# Power.net
KiCad netlist of a schematic drawn in Altium Designer
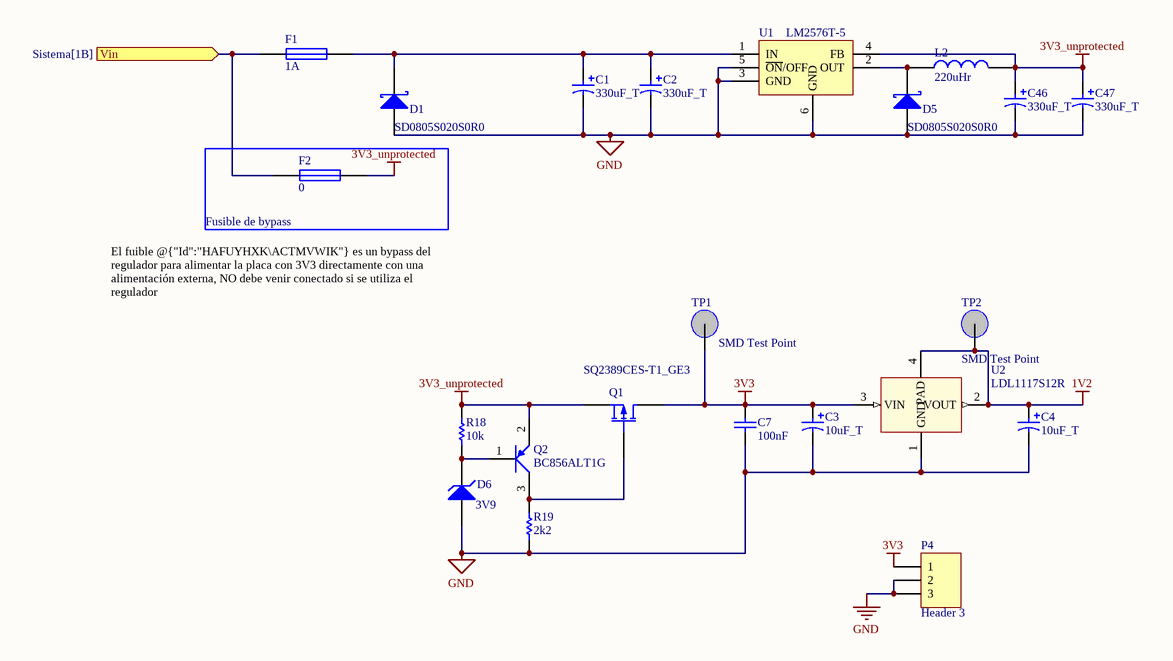
[diagram p0: Power.SchDoc]

(export (version "E")
  (design (tool "Eeschema 10.0.6"))
  (components
    (comp (ref "C1")
      (value "330uF_T")
      (footprint "C_2917")
      (description "Capacitor SMD 2917 Tant,TPME337*016#0050")
      (fields
        (field (name "MANUFACTURER") "Vishay")
        (field (name "MANUFACTURER PART NUMBER") "TMCP1A106MTRF")
      )
      (libsource (lib "Mi_lib") (part "C_330uF_tant_16V"))
    )
    (comp (ref "C2")
      (value "330uF_T")
      (footprint "C_2917")
      (description "Capacitor SMD 2917 Tant")
      (fields
        (field (name "MANUFACTURER") "Vishay")
        (field (name "MANUFACTURER PART NUMBER") "TMCP1A106MTRF")
      )
      (libsource (lib "Mi_lib") (part "C_330uF_tant_16V"))
    )
    (comp (ref "C3")
      (value "10uF_T")
      (footprint "C_0805_2013_c")
      (description "Capacitor SMD 0805 Tant")
      (fields
        (field (name "MANUFACTURER") "Vishay")
        (field (name "MANUFACTURER PART NUMBER") "TMCP1A106MTRF")
      )
      (libsource (lib "MyLibraryV2") (part "C_10uF_10V_b"))
    )
    (comp (ref "C4")
      (value "10uF_T")
      (footprint "C_0805_2013_c")
      (description "Capacitor SMD 0805 Tant")
      (fields
        (field (name "MANUFACTURER") "Vishay")
        (field (name "MANUFACTURER PART NUMBER") "TMCP1A106MTRF")
      )
      (libsource (lib "MyLibraryV2") (part "C_10uF_10V_b"))
    )
    (comp (ref "C7")
      (value "100nF")
      (footprint "C_0805_2013_b")
      (description "Capacitor SMD 0805")
      (fields (field (name "TOLERANCE") "10%") (field (name "VOLTAGE") "50V"))
      (libsource (lib "MyLibraryV2") (part "C_100nF_50V_b"))
    )
    (comp (ref "C46")
      (value "330uF_T")
      (footprint "C_2917")
      (description "Capacitor SMD 2917 Tant")
      (fields
        (field (name "MANUFACTURER") "Vishay")
        (field (name "MANUFACTURER PART NUMBER") "TMCP1A106MTRF")
      )
      (libsource (lib "Mi_lib") (part "C_330uF_tant_16V"))
    )
    (comp (ref "C47")
      (value "330uF_T")
      (footprint "C_2917")
      (description "Capacitor SMD 2917 Tant")
      (fields
        (field (name "MANUFACTURER") "Vishay")
        (field (name "MANUFACTURER PART NUMBER") "TMCP1A106MTRF")
      )
      (libsource (lib "Mi_lib") (part "C_330uF_tant_16V"))
    )
    (comp (ref "D1")
      (value "SD0805S020S0R0")
      (footprint "D_SOD-123")
      (description "Diode SMD D_SD0805S020S0R5")
      (fields (field (name "MANUFACTURER") "Diodes") (field (name "MANUFACTURER PART NUMBER") "B550C-13-F"))
      (libsource (lib "Mi_lib") (part "D_SD0805S020S0R5"))
    )
    (comp (ref "D5")
      (value "SD0805S020S0R0")
      (footprint "D_SOD-123")
      (description "Diode SMD D_SD0805S020S0R5")
      (fields (field (name "MANUFACTURER") "Diodes") (field (name "MANUFACTURER PART NUMBER") "B550C-13-F"))
      (libsource (lib "Mi_lib") (part "D_SD0805S020S0R5"))
    )
    (comp (ref "D6")
      (value "3V9")
      (footprint "D_SOD-123")
      (description "Zener Diode")
      (fields (field (name "TOLERANCE") "3%") (field (name "MANUFACTURER") "Diodes"))
      (libsource (lib "MyLibraryV2") (part "D_DDZ5V1B-7"))
    )
    (comp (ref "F1")
      (value "1A")
      (footprint "F_0805_2012")
      (description "(Generico) Fuse SMD 0805")
      (fields (field (name "PUBLISHER") "Altium Limited"))
      (libsource (lib "MyLibraryV2") (part "F_?_0805"))
    )
    (comp (ref "F2")
      (value "0")
      (footprint "F_0805_2012")
      (description "(Generico) Fuse SMD 0805")
      (fields (field (name "PUBLISHER") "Altium Limited"))
      (libsource (lib "MyLibraryV2") (part "F_?_0805"))
    )
    (comp (ref "L2")
      (value "220uHr")
      (footprint "L_SMD_10x10")
      (description "(Generico)  Inductor SMD 10x10")
      (libsource (lib "MyLibraryV2") (part "L_?_5"))
    )
    (comp (ref "P4")
      (value "Header 3")
      (footprint "P_HDR1X3_3D")
      (description "Header, 3-Pin")
      (libsource (lib "MyLibraryV2") (part "P_Header 3"))
    )
    (comp (ref "Q1")
      (value "SQ2389CES-T1_GE3")
      (footprint "Q_SOT-23")
      (libsource (lib "Mi_lib") (part "Q_SQ2389CES-T1_GE3"))
    )
    (comp (ref "Q2")
      (value "BC856ALT1G")
      (footprint "Q_SOT-23B_N")
      (description "TRANS PNP 65V 0.1A SOT23")
      (fields (field (name "MANUFACTURER") "ON Semiconductor"))
      (libsource (lib "MyLibraryV2") (part "Q_BC856"))
    )
    (comp (ref "R18")
      (value "10k")
      (footprint "R_0805_2012_a")
      (description "Resistor SMD 0805")
      (fields (field (name "TOLERANCE") "1%") (field (name "MANUFACTURER") "Yageo"))
      (libsource (lib "MyLibraryV2") (part "R_10k_b"))
    )
    (comp (ref "R19")
      (value "2k2")
      (footprint "R_0805_2012_a")
      (description "Resistor SMD 0805")
      (fields (field (name "TOLERANCE") "1%") (field (name "MANUFACTURER") "Bourns"))
      (libsource (lib "MyLibraryV2") (part "R_2k2_b"))
    )
    (comp (ref "TP1")
      (value "SMD Test Point")
      (footprint "TP SMD")
      (description "Test Point SMD")
      (fields (field (name "PUBLISHER") "Altium Limited"))
      (libsource (lib "MyLibraryV2") (part "P_T_TP"))
    )
    (comp (ref "TP2")
      (value "SMD Test Point")
      (footprint "TP SMD")
      (description "Test Point SMD")
      (fields (field (name "PUBLISHER") "Altium Limited"))
      (libsource (lib "MyLibraryV2") (part "P_T_TP"))
    )
    (comp (ref "U1")
      (value "LM2576T-5")
      (footprint "U_SMD_TO-263-5")
      (libsource (lib "MyLibraryV2") (part "U_LM2576-3.3WU"))
    )
    (comp (ref "U2")
      (value "LDL1117S12R")
      (footprint "U_SOT-223")
      (description "LDL1117 Series 1.2 A 2.5 V High PSRR LDO Linear Voltage Regulator-SOT-223")
      (fields
        (field (name "MANUFACTURER") "STMicroelectronics")
        (field (name "MANUFACTURER PART NUMBER") "LDL1117S25R")
      )
      (libsource (lib "MyLibraryV2") (part "U_LDL1117"))
    )
  )
  (nets
    (net (code "1") (name "/Vin") (class "Default")
      (node (ref "F1") (pin "1") (pinfunction "1_1") (pintype "passive"))
      (node (ref "F2") (pin "1") (pinfunction "1_1") (pintype "passive"))
    )
    (net (code "2") (name "1V2") (class "Default")
      (node (ref "C4") (pin "1") (pinfunction "1_1") (pintype "passive"))
      (node (ref "TP2") (pin "1") (pinfunction "1_1") (pintype "passive"))
      (node (ref "U2") (pin "2") (pinfunction "VOUT_2") (pintype "output"))
      (node (ref "U2") (pin "4") (pinfunction "PAD_4") (pintype "passive"))
    )
    (net (code "3") (name "3V3") (class "Default")
      (node (ref "C3") (pin "1") (pinfunction "1_1") (pintype "passive"))
      (node (ref "C7") (pin "2") (pinfunction "2_2") (pintype "passive"))
      (node (ref "P4") (pin "1") (pinfunction "1_1") (pintype "passive"))
      (node (ref "Q1") (pin "3") (pinfunction "D_3") (pintype "passive"))
      (node (ref "TP1") (pin "1") (pinfunction "1_1") (pintype "passive"))
      (node (ref "U2") (pin "3") (pinfunction "VIN_3") (pintype "input"))
    )
    (net (code "4") (name "3V3_unprotected") (class "Default")
      (node (ref "C46") (pin "1") (pinfunction "1_1") (pintype "passive"))
      (node (ref "C47") (pin "1") (pinfunction "1_1") (pintype "passive"))
      (node (ref "F2") (pin "2") (pinfunction "2_2") (pintype "passive"))
      (node (ref "L2") (pin "2") (pinfunction "2_2") (pintype "passive"))
      (node (ref "Q1") (pin "2") (pinfunction "S_2") (pintype "passive"))
      (node (ref "Q2") (pin "2") (pinfunction "E_2") (pintype "passive"))
      (node (ref "R18") (pin "2") (pinfunction "2_2") (pintype "passive"))
      (node (ref "U1") (pin "4") (pinfunction "FB_4") (pintype "passive"))
    )
    (net (code "5") (name "GND") (class "Default")
      (node (ref "C1") (pin "2") (pinfunction "2_2") (pintype "passive"))
      (node (ref "C2") (pin "2") (pinfunction "2_2") (pintype "passive"))
      (node (ref "C3") (pin "2") (pinfunction "2_2") (pintype "passive"))
      (node (ref "C4") (pin "2") (pinfunction "2_2") (pintype "passive"))
      (node (ref "C46") (pin "2") (pinfunction "2_2") (pintype "passive"))
      (node (ref "C47") (pin "2") (pinfunction "2_2") (pintype "passive"))
      (node (ref "C7") (pin "1") (pinfunction "1_1") (pintype "passive"))
      (node (ref "D1") (pin "2") (pinfunction "A_2") (pintype "passive"))
      (node (ref "D5") (pin "2") (pinfunction "A_2") (pintype "passive"))
      (node (ref "D6") (pin "2") (pinfunction "A_2") (pintype "passive"))
      (node (ref "P4") (pin "2") (pinfunction "2_2") (pintype "passive"))
      (node (ref "P4") (pin "3") (pinfunction "3_3") (pintype "passive"))
      (node (ref "R19") (pin "2") (pinfunction "2_2") (pintype "passive"))
      (node (ref "U1") (pin "3") (pinfunction "GND_3") (pintype "passive"))
      (node (ref "U1") (pin "5") (pinfunction "~{ON}/OFF_5") (pintype "passive"))
      (node (ref "U1") (pin "6") (pinfunction "GND_6") (pintype "passive"))
      (node (ref "U2") (pin "1") (pinfunction "GND_1") (pintype "power_in"))
    )
    (net (code "6") (name "Net-(D1-K)") (class "Default")
      (node (ref "C1") (pin "1") (pinfunction "1_1") (pintype "passive"))
      (node (ref "C2") (pin "1") (pinfunction "1_1") (pintype "passive"))
      (node (ref "D1") (pin "1") (pinfunction "K_1") (pintype "passive"))
      (node (ref "F1") (pin "2") (pinfunction "2_2") (pintype "passive"))
      (node (ref "U1") (pin "1") (pinfunction "IN_1") (pintype "passive"))
    )
    (net (code "7") (name "Net-(D5-K)") (class "Default")
      (node (ref "D5") (pin "1") (pinfunction "K_1") (pintype "passive"))
      (node (ref "L2") (pin "1") (pinfunction "1_1") (pintype "passive"))
      (node (ref "U1") (pin "2") (pinfunction "OUT_2") (pintype "passive"))
    )
    (net (code "8") (name "Net-(D6-K)") (class "Default")
      (node (ref "D6") (pin "1") (pinfunction "K_1") (pintype "passive"))
      (node (ref "Q2") (pin "1") (pinfunction "B_1") (pintype "passive"))
      (node (ref "R18") (pin "1") (pinfunction "1_1") (pintype "passive"))
    )
    (net (code "9") (name "Net-(Q1-G)") (class "Default")
      (node (ref "Q1") (pin "1") (pinfunction "G_1") (pintype "passive"))
      (node (ref "Q2") (pin "3") (pinfunction "C_3") (pintype "passive"))
      (node (ref "R19") (pin "1") (pinfunction "1_1") (pintype "passive"))
    )
  )
)
